# JD-T1800_Display_Breakout.net
KiCad netlist of a schematic drawn in EAGLE
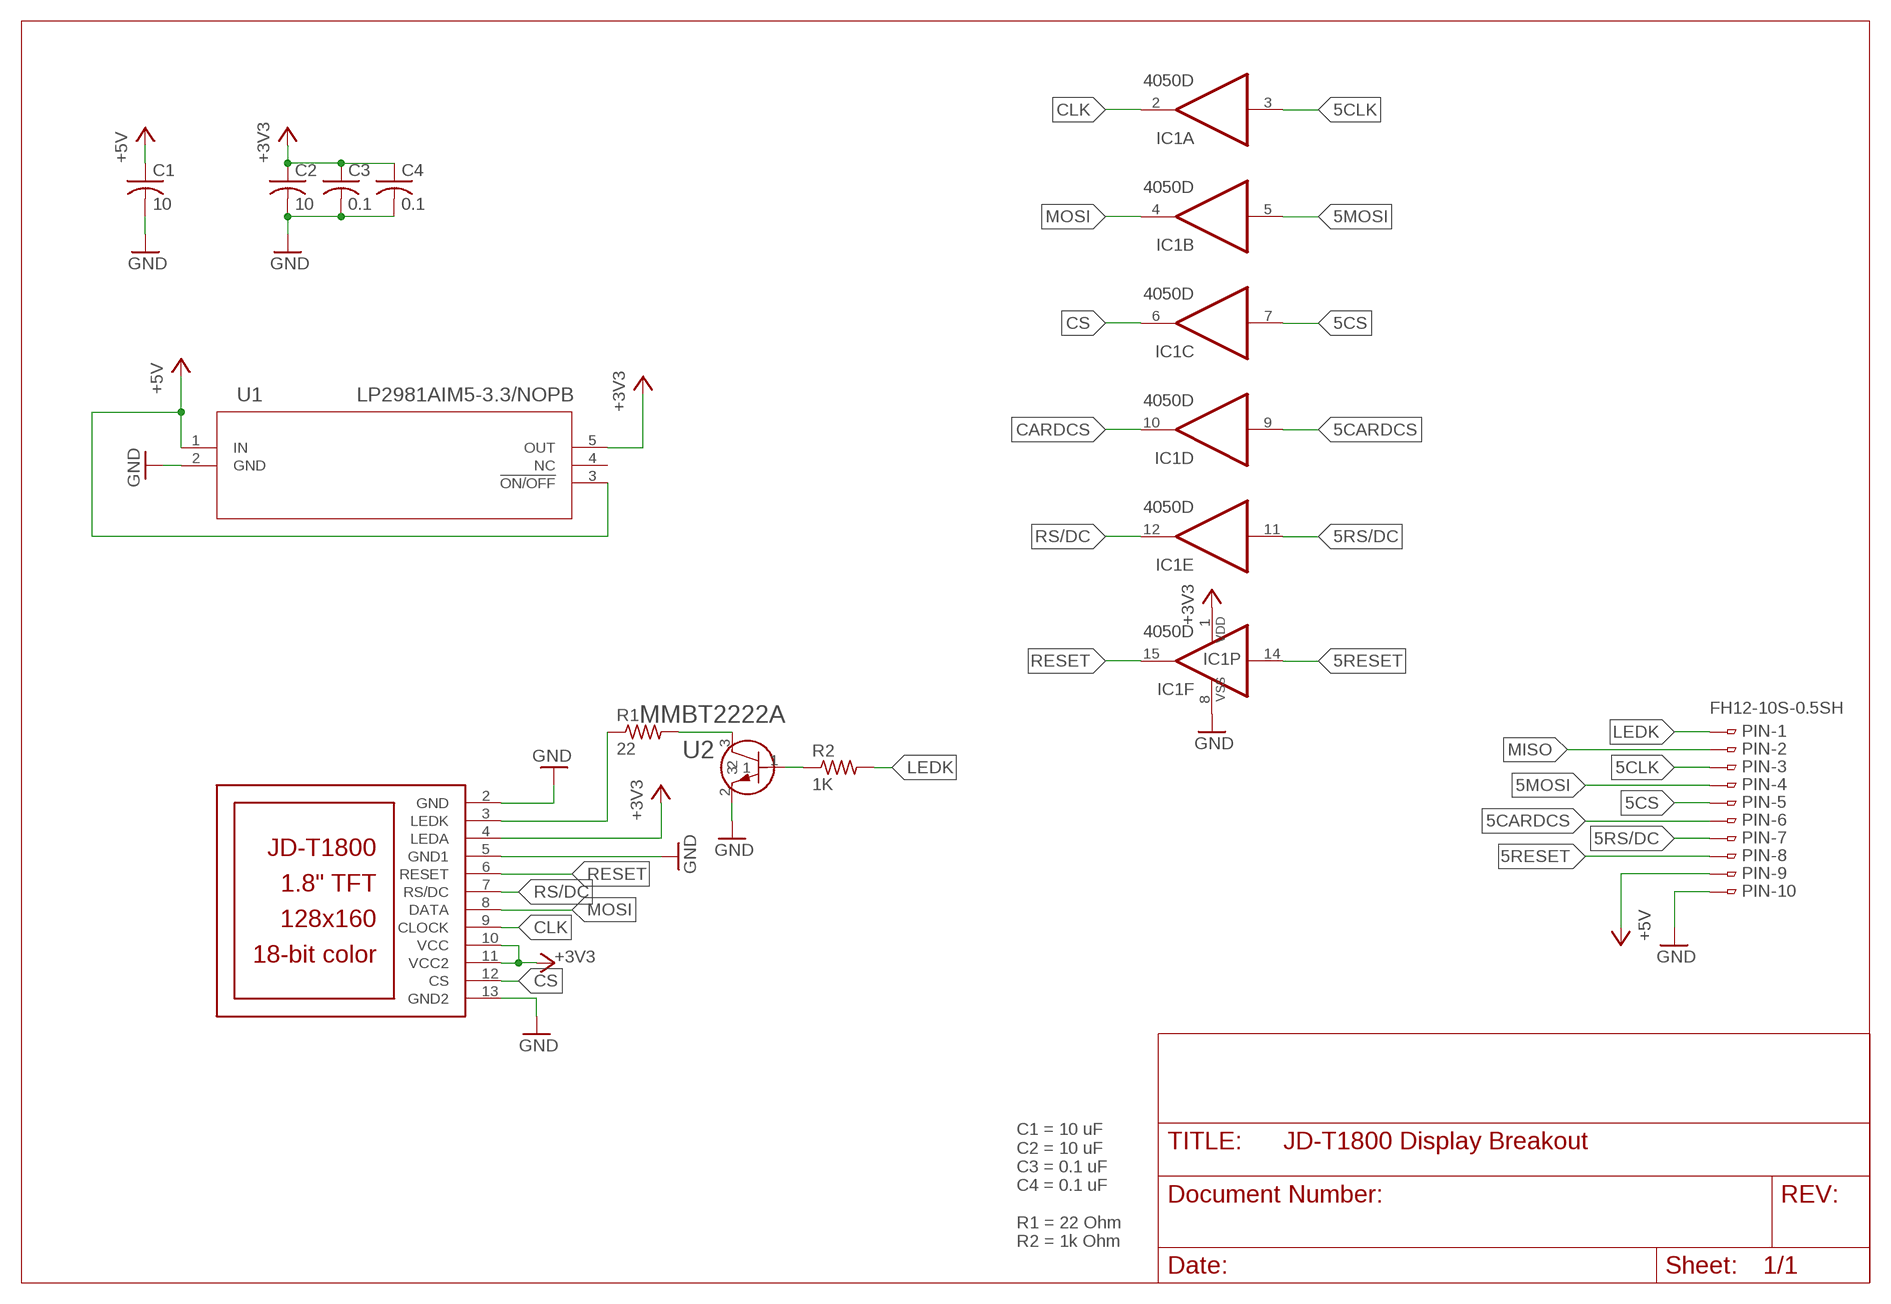
[diagram p0: schematic, sheet 1]

(export (version "E")
  (design (tool "Eeschema 10.0.6"))
  (components
    (comp (ref "C1")
      (value "10")
      (footprint "eagle-import:C0805")
      (libsource (lib "eagle-import") (part "C-USC0805"))
    )
    (comp (ref "C2")
      (value "10")
      (footprint "eagle-import:C0805")
      (libsource (lib "eagle-import") (part "C-USC0805"))
    )
    (comp (ref "C3")
      (value "0.1")
      (footprint "eagle-import:C0805")
      (libsource (lib "eagle-import") (part "C-USC0805"))
    )
    (comp (ref "C4")
      (value "0.1")
      (footprint "eagle-import:C0805")
      (libsource (lib "eagle-import") (part "C-USC0805"))
    )
    (comp (ref "IC1")
      (value "4050D")
      (footprint "eagle-import:SO16")
      (libsource (lib "eagle-import") (part "4050D"))
    )
    (comp (ref "PIN")
      (value "FH12-10S-0.5SH")
      (footprint "eagle-import:FH12-10S-0.5SH")
      (fields (field (name "MPN") "FH12-10S-0.5SH(55)"))
      (libsource (lib "eagle-import") (part "FH12-10S-0.5SH"))
    )
    (comp (ref "R1")
      (value "22")
      (footprint "eagle-import:R0805")
      (libsource (lib "eagle-import") (part "R-US_R0805"))
    )
    (comp (ref "R2")
      (value "1K")
      (footprint "eagle-import:R0805")
      (libsource (lib "eagle-import") (part "R-US_R0805"))
    )
    (comp (ref "U$1")
      (value "JD-T1800")
      (footprint "eagle-import:JD-T1800")
      (libsource (lib "eagle-import") (part "JD-T1800"))
    )
    (comp (ref "U1")
      (value "LP2981AIM5-3.3/NOPB")
      (footprint "eagle-import:MF05A")
      (fields (field (name "MANUFACTURER_PART_NUMBER") "LP2981AIM53.3NOPB"))
      (libsource (lib "eagle-import") (part "LP2981AIM5-3.3/NOPB"))
    )
    (comp (ref "U2")
      (value "MMBT2222A")
      (footprint "eagle-import:SOT23")
      (libsource (lib "eagle-import") (part "MMBT2222A"))
    )
  )
  (nets
    (net (code "1") (name "+3V3") (class "Default")
      (node (ref "C2") (pin "1") (pinfunction "1_1") (pintype "passive"))
      (node (ref "C3") (pin "1") (pinfunction "1_1") (pintype "passive"))
      (node (ref "C4") (pin "1") (pinfunction "1_1") (pintype "passive"))
      (node (ref "IC1") (pin "1") (pinfunction "VDD_1") (pintype "power_in"))
      (node (ref "U$1") (pin "10") (pinfunction "VCC_10") (pintype "power_in"))
      (node (ref "U$1") (pin "11") (pinfunction "VCC2_11") (pintype "power_in"))
      (node (ref "U$1") (pin "4") (pinfunction "LEDA_4") (pintype "input"))
      (node (ref "U1") (pin "5") (pinfunction "OUT_5") (pintype "power_in"))
    )
    (net (code "2") (name "+5V") (class "Default")
      (node (ref "C1") (pin "1") (pinfunction "1_1") (pintype "passive"))
      (node (ref "PIN") (pin "9") (pinfunction "1_9") (pintype "passive"))
      (node (ref "U1") (pin "1") (pinfunction "IN_1") (pintype "power_in"))
      (node (ref "U1") (pin "3") (pinfunction "~{ON/OFF}_3") (pintype "input"))
    )
    (net (code "3") (name "5CARDCS") (class "Default")
      (node (ref "IC1") (pin "9") (pinfunction "I_9") (pintype "input"))
      (node (ref "PIN") (pin "6") (pinfunction "1_6") (pintype "passive"))
    )
    (net (code "4") (name "5CLK") (class "Default")
      (node (ref "IC1") (pin "3") (pinfunction "I_3") (pintype "input"))
      (node (ref "PIN") (pin "3") (pinfunction "1_3") (pintype "passive"))
    )
    (net (code "5") (name "5CS") (class "Default")
      (node (ref "IC1") (pin "7") (pinfunction "I_7") (pintype "input"))
      (node (ref "PIN") (pin "5") (pinfunction "1_5") (pintype "passive"))
    )
    (net (code "6") (name "5MOSI") (class "Default")
      (node (ref "IC1") (pin "5") (pinfunction "I_5") (pintype "input"))
      (node (ref "PIN") (pin "4") (pinfunction "1_4") (pintype "passive"))
    )
    (net (code "7") (name "5RESET") (class "Default")
      (node (ref "IC1") (pin "14") (pinfunction "I_14") (pintype "input"))
      (node (ref "PIN") (pin "8") (pinfunction "1_8") (pintype "passive"))
    )
    (net (code "8") (name "5RS{slash}DC") (class "Default")
      (node (ref "IC1") (pin "11") (pinfunction "I_11") (pintype "input"))
      (node (ref "PIN") (pin "7") (pinfunction "1_7") (pintype "passive"))
    )
    (net (code "9") (name "CARDCS") (class "Default")
      (node (ref "IC1") (pin "10") (pinfunction "O_10") (pintype "output"))
    )
    (net (code "10") (name "CLK") (class "Default")
      (node (ref "IC1") (pin "2") (pinfunction "O_2") (pintype "output"))
      (node (ref "U$1") (pin "9") (pinfunction "CLOCK_9") (pintype "input"))
    )
    (net (code "11") (name "CS") (class "Default")
      (node (ref "IC1") (pin "6") (pinfunction "O_6") (pintype "output"))
      (node (ref "U$1") (pin "12") (pinfunction "CS_12") (pintype "input"))
    )
    (net (code "12") (name "GND") (class "Default")
      (node (ref "C1") (pin "2") (pinfunction "2_2") (pintype "passive"))
      (node (ref "C2") (pin "2") (pinfunction "2_2") (pintype "passive"))
      (node (ref "C3") (pin "2") (pinfunction "2_2") (pintype "passive"))
      (node (ref "C4") (pin "2") (pinfunction "2_2") (pintype "passive"))
      (node (ref "IC1") (pin "8") (pinfunction "VSS_8") (pintype "power_in"))
      (node (ref "PIN") (pin "10") (pinfunction "1_10") (pintype "passive"))
      (node (ref "U$1") (pin "13") (pinfunction "GND2_13") (pintype "power_in"))
      (node (ref "U$1") (pin "2") (pinfunction "GND_2") (pintype "power_in"))
      (node (ref "U$1") (pin "5") (pinfunction "GND1_5") (pintype "power_in"))
      (node (ref "U1") (pin "2") (pinfunction "GND_2") (pintype "power_in"))
      (node (ref "U2") (pin "2") (pinfunction "2_2") (pintype "passive"))
    )
    (net (code "13") (name "LEDK") (class "Default")
      (node (ref "PIN") (pin "1") (pinfunction "1_1") (pintype "passive"))
      (node (ref "R2") (pin "2") (pinfunction "2_2") (pintype "passive"))
    )
    (net (code "14") (name "MISO") (class "Default")
      (node (ref "PIN") (pin "2") (pinfunction "1_2") (pintype "passive"))
    )
    (net (code "15") (name "MOSI") (class "Default")
      (node (ref "IC1") (pin "4") (pinfunction "O_4") (pintype "output"))
      (node (ref "U$1") (pin "8") (pinfunction "DATA_8") (pintype "bidirectional"))
    )
    (net (code "16") (name "Net-(R1-Pad2)") (class "Default")
      (node (ref "R1") (pin "2") (pinfunction "2_2") (pintype "passive"))
      (node (ref "U2") (pin "3") (pinfunction "3_3") (pintype "passive"))
    )
    (net (code "17") (name "Net-(R2-Pad1)") (class "Default")
      (node (ref "R2") (pin "1") (pinfunction "1_1") (pintype "passive"))
      (node (ref "U2") (pin "1") (pinfunction "1_1") (pintype "passive"))
    )
    (net (code "18") (name "Net-(U$1-LEDK)") (class "Default")
      (node (ref "R1") (pin "1") (pinfunction "1_1") (pintype "passive"))
      (node (ref "U$1") (pin "3") (pinfunction "LEDK_3") (pintype "input"))
    )
    (net (code "19") (name "RESET") (class "Default")
      (node (ref "IC1") (pin "15") (pinfunction "O_15") (pintype "output"))
      (node (ref "U$1") (pin "6") (pinfunction "RESET_6") (pintype "input"))
    )
    (net (code "20") (name "RS{slash}DC") (class "Default")
      (node (ref "IC1") (pin "12") (pinfunction "O_12") (pintype "output"))
      (node (ref "U$1") (pin "7") (pinfunction "RS/DC_7") (pintype "input"))
    )
    (net (code "21") (name "unconnected-(U1-NC-Pad4)") (class "Default")
      (node (ref "U1") (pin "4") (pinfunction "NC_4") (pintype "passive"))
    )
  )
)
